# SB2232_v02.net
KiCad netlist of a schematic drawn in Altium Designer
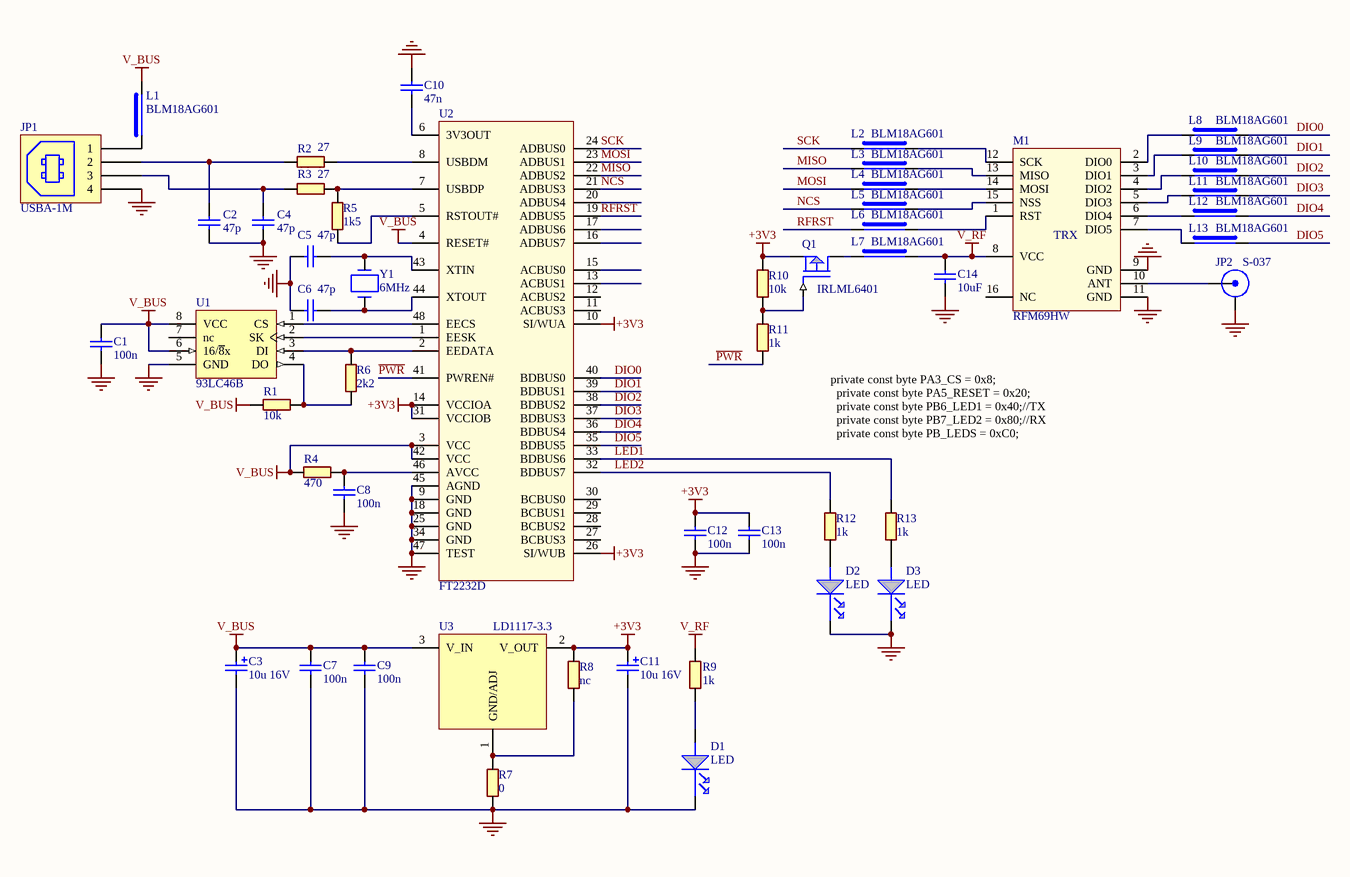
[diagram p0: SB2232_v02.SchDoc]

(export (version "E")
  (design (tool "Eeschema 10.0.6"))
  (components
    (comp (ref "C1") (value "100n") (footprint "CAPC1608X08N") (libsource (lib "Discrete") (part "CAPN")))
    (comp (ref "C2") (value "47p") (footprint "CAPC1608X08N") (libsource (lib "Discrete") (part "CAPN")))
    (comp (ref "C3") (value "10u 16V") (footprint "CAPMP3217X18N") (libsource (lib "Discrete") (part "CAPP")))
    (comp (ref "C4") (value "47p") (footprint "CAPC1608X08N") (libsource (lib "Discrete") (part "CAPN")))
    (comp (ref "C5") (value "47p") (footprint "CAPC1608X08N") (libsource (lib "Discrete") (part "CAPN")))
    (comp (ref "C6") (value "47p") (footprint "CAPC1608X08N") (libsource (lib "Discrete") (part "CAPN")))
    (comp (ref "C7") (value "100n") (footprint "CAPC1608X08N") (libsource (lib "Discrete") (part "CAPN")))
    (comp (ref "C8") (value "100n") (footprint "CAPC1608X08N") (libsource (lib "Discrete") (part "CAPN")))
    (comp (ref "C9") (value "100n") (footprint "CAPC1608X08N") (libsource (lib "Discrete") (part "CAPN")))
    (comp (ref "C10") (value "47n") (footprint "CAPC1608X08N") (libsource (lib "Discrete") (part "CAPN")))
    (comp (ref "C11")
      (value "10u 16V")
      (footprint "CAPMP3217X18N")
      (libsource (lib "Discrete") (part "CAPP"))
    )
    (comp (ref "C12") (value "100n") (footprint "CAPC1608X08N") (libsource (lib "Discrete") (part "CAPN")))
    (comp (ref "C13") (value "100n") (footprint "CAPC1608X08N") (libsource (lib "Discrete") (part "CAPN")))
    (comp (ref "C14") (value "10uF") (footprint "CAPC2012X11N") (libsource (lib "Discrete") (part "CAPN")))
    (comp (ref "D1") (value "LED") (footprint "LEDC200X125X80L40N") (libsource (lib "Discrete") (part "LED")))
    (comp (ref "D2") (value "LED") (footprint "LEDC200X125X80L40N") (libsource (lib "Discrete") (part "LED")))
    (comp (ref "D3") (value "LED") (footprint "LEDC200X125X80L40N") (libsource (lib "Discrete") (part "LED")))
    (comp (ref "JP1")
      (value "USBA-1M")
      (footprint "USB_A_M_SMD")
      (description "USB_connector")
      (libsource (lib "jlink072") (part "USB_conn"))
    )
    (comp (ref "JP2")
      (value "S-037")
      (footprint "S-037_3D")
      (description "RF Connector")
      (libsource (lib "RFM_PS_V01") (part "BNC"))
    )
    (comp (ref "L1")
      (value "BLM18AG601")
      (footprint "INDC1608X10N")
      (libsource (lib "RFM_PS_V01") (part "SUPRESOR"))
    )
    (comp (ref "L2")
      (value "BLM18AG601")
      (footprint "INDC1608X10N")
      (libsource (lib "RFM_PS_V01") (part "SUPRESOR"))
    )
    (comp (ref "L3")
      (value "BLM18AG601")
      (footprint "INDC1608X10N")
      (libsource (lib "RFM_PS_V01") (part "SUPRESOR"))
    )
    (comp (ref "L4")
      (value "BLM18AG601")
      (footprint "INDC1608X10N")
      (libsource (lib "RFM_PS_V01") (part "SUPRESOR"))
    )
    (comp (ref "L5")
      (value "BLM18AG601")
      (footprint "INDC1608X10N")
      (libsource (lib "RFM_PS_V01") (part "SUPRESOR"))
    )
    (comp (ref "L6")
      (value "BLM18AG601")
      (footprint "INDC1608X10N")
      (libsource (lib "RFM_PS_V01") (part "SUPRESOR"))
    )
    (comp (ref "L7")
      (value "BLM18AG601")
      (footprint "INDC1608X10N")
      (libsource (lib "RFM_PS_V01") (part "SUPRESOR"))
    )
    (comp (ref "L8")
      (value "BLM18AG601")
      (footprint "INDC1608X10N")
      (libsource (lib "RFM_PS_V01") (part "SUPRESOR"))
    )
    (comp (ref "L9")
      (value "BLM18AG601")
      (footprint "INDC1608X10N")
      (libsource (lib "RFM_PS_V01") (part "SUPRESOR"))
    )
    (comp (ref "L10")
      (value "BLM18AG601")
      (footprint "INDC1608X10N")
      (libsource (lib "RFM_PS_V01") (part "SUPRESOR"))
    )
    (comp (ref "L11")
      (value "BLM18AG601")
      (footprint "INDC1608X10N")
      (libsource (lib "RFM_PS_V01") (part "SUPRESOR"))
    )
    (comp (ref "L12")
      (value "BLM18AG601")
      (footprint "INDC1608X10N")
      (libsource (lib "RFM_PS_V01") (part "SUPRESOR"))
    )
    (comp (ref "L13")
      (value "BLM18AG601")
      (footprint "INDC1608X10N")
      (libsource (lib "RFM_PS_V01") (part "SUPRESOR"))
    )
    (comp (ref "M1")
      (value "RFM69HW")
      (footprint "LGA16_RFM69")
      (libsource (lib "CLAP_M505_WL_BP_V22") (part "RFM69HW_V13_2"))
    )
    (comp (ref "Q1")
      (value "IRLML6401")
      (footprint "SOT-23")
      (libsource (lib "CLAP_M505_WL_BP_V22") (part "MOSF-P"))
    )
    (comp (ref "R1") (value "10k") (footprint "RESC1608X06N") (libsource (lib "") (part "RES_2")))
    (comp (ref "R2") (value "27") (footprint "RESC1608X06N") (libsource (lib "") (part "RES_1")))
    (comp (ref "R3") (value "27") (footprint "RESC1608X06N") (libsource (lib "") (part "RES_1")))
    (comp (ref "R4") (value "470") (footprint "RESC1608X06N") (libsource (lib "") (part "RES_1")))
    (comp (ref "R5") (value "1k5") (footprint "RESC1608X06N") (libsource (lib "Discrete") (part "RES")))
    (comp (ref "R6") (value "2k2") (footprint "RESC1608X06N") (libsource (lib "Discrete") (part "RES")))
    (comp (ref "R7") (value "0") (footprint "RESC1608X06N") (libsource (lib "Discrete") (part "RES")))
    (comp (ref "R8") (value "nc") (footprint "RESC1608X06N") (libsource (lib "Discrete") (part "RES")))
    (comp (ref "R9") (value "1k") (footprint "RESC1608X06N") (libsource (lib "") (part "RES_3")))
    (comp (ref "R10") (value "10k") (footprint "RESC1608X06N") (libsource (lib "Discrete") (part "RES")))
    (comp (ref "R11") (value "1k") (footprint "RESC1608X06N") (libsource (lib "Discrete") (part "RES")))
    (comp (ref "R12") (value "1k") (footprint "RESC1608X06N") (libsource (lib "") (part "RES_3")))
    (comp (ref "R13") (value "1k") (footprint "RESC1608X06N") (libsource (lib "Discrete") (part "RES")))
    (comp (ref "U1")
      (value "93LC46B")
      (footprint "SOIC127P600X175-8N")
      (description "3-wire EEPROM")
      (libsource (lib "ICs") (part "93C56"))
    )
    (comp (ref "U2")
      (value "FT2232D")
      (footprint "TSQFP50P900X900X160-48N")
      (libsource (lib "SB") (part "FT2232D"))
    )
    (comp (ref "U3")
      (value "LD1117-3.3")
      (footprint "SOT230P700X180-4N")
      (libsource (lib "RFM_PS_V01") (part "LM1117_3.3"))
    )
    (comp (ref "Y1")
      (value "6MHz")
      (footprint "XTAL_HC49P488W45L1117T490H350")
      (libsource (lib "Discrete") (part "Y"))
    )
  )
  (nets
    (net (code "1") (name "+3V3") (class "Default")
      (node (ref "C11") (pin "2") (pinfunction "2_2") (pintype "passive"))
      (node (ref "C12") (pin "1") (pinfunction "1_1") (pintype "passive"))
      (node (ref "C13") (pin "1") (pinfunction "1_1") (pintype "passive"))
      (node (ref "Q1") (pin "3") (pinfunction "SOURCE_3") (pintype "passive"))
      (node (ref "R10") (pin "2") (pinfunction "2_2") (pintype "passive"))
      (node (ref "R8") (pin "2") (pinfunction "2_2") (pintype "passive"))
      (node (ref "U2") (pin "10") (pinfunction "SI/WUA_10") (pintype "passive"))
      (node (ref "U2") (pin "14") (pinfunction "VCCIOA_14") (pintype "passive"))
      (node (ref "U2") (pin "26") (pinfunction "SI/WUB_26") (pintype "passive"))
      (node (ref "U2") (pin "31") (pinfunction "VCCIOB_31") (pintype "passive"))
      (node (ref "U3") (pin "2") (pinfunction "V_OUT_2") (pintype "passive"))
    )
    (net (code "2") (name "/DIO0") (class "Default")
      (node (ref "L8") (pin "2") (pinfunction "2_2") (pintype "passive"))
      (node (ref "U2") (pin "40") (pinfunction "BDBUS0_40") (pintype "passive"))
    )
    (net (code "3") (name "/DIO1") (class "Default")
      (node (ref "L9") (pin "2") (pinfunction "2_2") (pintype "passive"))
      (node (ref "U2") (pin "39") (pinfunction "BDBUS1_39") (pintype "passive"))
    )
    (net (code "4") (name "/DIO2") (class "Default")
      (node (ref "L10") (pin "2") (pinfunction "2_2") (pintype "passive"))
      (node (ref "U2") (pin "38") (pinfunction "BDBUS2_38") (pintype "passive"))
    )
    (net (code "5") (name "/DIO3") (class "Default")
      (node (ref "L11") (pin "2") (pinfunction "2_2") (pintype "passive"))
      (node (ref "U2") (pin "37") (pinfunction "BDBUS3_37") (pintype "passive"))
    )
    (net (code "6") (name "/DIO4") (class "Default")
      (node (ref "L12") (pin "2") (pinfunction "2_2") (pintype "passive"))
      (node (ref "U2") (pin "36") (pinfunction "BDBUS4_36") (pintype "passive"))
    )
    (net (code "7") (name "/DIO5") (class "Default")
      (node (ref "L13") (pin "2") (pinfunction "2_2") (pintype "passive"))
      (node (ref "U2") (pin "35") (pinfunction "BDBUS5_35") (pintype "passive"))
    )
    (net (code "8") (name "/LED1") (class "Default")
      (node (ref "R13") (pin "2") (pinfunction "2_2") (pintype "passive"))
      (node (ref "U2") (pin "33") (pinfunction "BDBUS6_33") (pintype "passive"))
    )
    (net (code "9") (name "/LED2") (class "Default")
      (node (ref "R12") (pin "1") (pinfunction "1_1") (pintype "passive"))
      (node (ref "U2") (pin "32") (pinfunction "BDBUS7_32") (pintype "passive"))
    )
    (net (code "10") (name "/MISO") (class "Default")
      (node (ref "L3") (pin "1") (pinfunction "1_1") (pintype "passive"))
      (node (ref "U2") (pin "22") (pinfunction "ADBUS2_22") (pintype "passive"))
    )
    (net (code "11") (name "/MOSI") (class "Default")
      (node (ref "L4") (pin "1") (pinfunction "1_1") (pintype "passive"))
      (node (ref "U2") (pin "23") (pinfunction "ADBUS1_23") (pintype "passive"))
    )
    (net (code "12") (name "/NCS") (class "Default")
      (node (ref "L5") (pin "1") (pinfunction "1_1") (pintype "passive"))
      (node (ref "U2") (pin "21") (pinfunction "ADBUS3_21") (pintype "passive"))
    )
    (net (code "13") (name "/RFRST") (class "Default")
      (node (ref "L6") (pin "1") (pinfunction "1_1") (pintype "passive"))
      (node (ref "U2") (pin "19") (pinfunction "ADBUS5_19") (pintype "passive"))
    )
    (net (code "14") (name "/SCK") (class "Default")
      (node (ref "L2") (pin "1") (pinfunction "1_1") (pintype "passive"))
      (node (ref "U2") (pin "24") (pinfunction "ADBUS0_24") (pintype "passive"))
    )
    (net (code "15") (name "/~{PWR}") (class "Default")
      (node (ref "R11") (pin "1") (pinfunction "1_1") (pintype "passive"))
      (node (ref "U2") (pin "41") (pinfunction "PWREN#_41") (pintype "passive"))
    )
    (net (code "16") (name "GND") (class "Default")
      (node (ref "C1") (pin "2") (pinfunction "2_2") (pintype "passive"))
      (node (ref "C10") (pin "1") (pinfunction "1_1") (pintype "passive"))
      (node (ref "C11") (pin "1") (pinfunction "1_1") (pintype "passive"))
      (node (ref "C12") (pin "2") (pinfunction "2_2") (pintype "passive"))
      (node (ref "C13") (pin "2") (pinfunction "2_2") (pintype "passive"))
      (node (ref "C14") (pin "2") (pinfunction "2_2") (pintype "passive"))
      (node (ref "C2") (pin "2") (pinfunction "2_2") (pintype "passive"))
      (node (ref "C3") (pin "1") (pinfunction "1_1") (pintype "passive"))
      (node (ref "C4") (pin "2") (pinfunction "2_2") (pintype "passive"))
      (node (ref "C5") (pin "1") (pinfunction "1_1") (pintype "passive"))
      (node (ref "C6") (pin "1") (pinfunction "1_1") (pintype "passive"))
      (node (ref "C7") (pin "2") (pinfunction "2_2") (pintype "passive"))
      (node (ref "C8") (pin "2") (pinfunction "2_2") (pintype "passive"))
      (node (ref "C9") (pin "2") (pinfunction "2_2") (pintype "passive"))
      (node (ref "D1") (pin "K") (pinfunction "CATHODE_K") (pintype "passive"))
      (node (ref "D2") (pin "K") (pinfunction "CATHODE_K") (pintype "passive"))
      (node (ref "D3") (pin "K") (pinfunction "CATHODE_K") (pintype "passive"))
      (node (ref "JP1") (pin "4") (pinfunction "4_4") (pintype "passive"))
      (node (ref "JP2") (pin "2") (pinfunction "Y_2") (pintype "passive"))
      (node (ref "M1") (pin "11") (pinfunction "GND_11") (pintype "passive"))
      (node (ref "M1") (pin "9") (pinfunction "GND_9") (pintype "passive"))
      (node (ref "R7") (pin "1") (pinfunction "1_1") (pintype "passive"))
      (node (ref "U1") (pin "5") (pinfunction "GND_5") (pintype "power_in"))
      (node (ref "U2") (pin "18") (pinfunction "GND_18") (pintype "passive"))
      (node (ref "U2") (pin "25") (pinfunction "GND_25") (pintype "passive"))
      (node (ref "U2") (pin "34") (pinfunction "GND_34") (pintype "passive"))
      (node (ref "U2") (pin "45") (pinfunction "AGND_45") (pintype "passive"))
      (node (ref "U2") (pin "47") (pinfunction "TEST_47") (pintype "passive"))
      (node (ref "U2") (pin "9") (pinfunction "GND_9") (pintype "passive"))
    )
    (net (code "17") (name "Net-(C2-Pad1)") (class "Default")
      (node (ref "C2") (pin "1") (pinfunction "1_1") (pintype "passive"))
      (node (ref "JP1") (pin "2") (pinfunction "2_2") (pintype "passive"))
      (node (ref "R2") (pin "1") (pinfunction "1_1") (pintype "passive"))
    )
    (net (code "18") (name "Net-(C4-Pad1)") (class "Default")
      (node (ref "C4") (pin "1") (pinfunction "1_1") (pintype "passive"))
      (node (ref "JP1") (pin "3") (pinfunction "3_3") (pintype "passive"))
      (node (ref "R3") (pin "1") (pinfunction "1_1") (pintype "passive"))
    )
    (net (code "19") (name "Net-(D1-ANODE)") (class "Default")
      (node (ref "D1") (pin "A") (pinfunction "ANODE_A") (pintype "passive"))
      (node (ref "R9") (pin "2") (pinfunction "2_2") (pintype "passive"))
    )
    (net (code "20") (name "Net-(D2-ANODE)") (class "Default")
      (node (ref "D2") (pin "A") (pinfunction "ANODE_A") (pintype "passive"))
      (node (ref "R12") (pin "2") (pinfunction "2_2") (pintype "passive"))
    )
    (net (code "21") (name "Net-(D3-ANODE)") (class "Default")
      (node (ref "D3") (pin "A") (pinfunction "ANODE_A") (pintype "passive"))
      (node (ref "R13") (pin "1") (pinfunction "1_1") (pintype "passive"))
    )
    (net (code "22") (name "Net-(JP1-Pad1)") (class "Default")
      (node (ref "JP1") (pin "1") (pinfunction "1_1") (pintype "passive"))
      (node (ref "L1") (pin "1") (pinfunction "1_1") (pintype "passive"))
    )
    (net (code "23") (name "Net-(JP2-X)") (class "Default")
      (node (ref "JP2") (pin "1") (pinfunction "X_1") (pintype "passive"))
      (node (ref "M1") (pin "10") (pinfunction "ANT_10") (pintype "passive"))
    )
    (net (code "24") (name "Net-(M1-DIO0)") (class "Default")
      (node (ref "L8") (pin "1") (pinfunction "1_1") (pintype "passive"))
      (node (ref "M1") (pin "2") (pinfunction "DIO0_2") (pintype "passive"))
    )
    (net (code "25") (name "Net-(M1-DIO1)") (class "Default")
      (node (ref "L9") (pin "1") (pinfunction "1_1") (pintype "passive"))
      (node (ref "M1") (pin "3") (pinfunction "DIO1_3") (pintype "passive"))
    )
    (net (code "26") (name "Net-(M1-DIO2)") (class "Default")
      (node (ref "L10") (pin "1") (pinfunction "1_1") (pintype "passive"))
      (node (ref "M1") (pin "4") (pinfunction "DIO2_4") (pintype "passive"))
    )
    (net (code "27") (name "Net-(M1-DIO3)") (class "Default")
      (node (ref "L11") (pin "1") (pinfunction "1_1") (pintype "passive"))
      (node (ref "M1") (pin "5") (pinfunction "DIO3_5") (pintype "passive"))
    )
    (net (code "28") (name "Net-(M1-DIO4)") (class "Default")
      (node (ref "L12") (pin "1") (pinfunction "1_1") (pintype "passive"))
      (node (ref "M1") (pin "6") (pinfunction "DIO4_6") (pintype "passive"))
    )
    (net (code "29") (name "Net-(M1-DIO5)") (class "Default")
      (node (ref "L13") (pin "1") (pinfunction "1_1") (pintype "passive"))
      (node (ref "M1") (pin "7") (pinfunction "DIO5_7") (pintype "passive"))
    )
    (net (code "30") (name "Net-(M1-MISO)") (class "Default")
      (node (ref "L3") (pin "2") (pinfunction "2_2") (pintype "passive"))
      (node (ref "M1") (pin "13") (pinfunction "MISO_13") (pintype "passive"))
    )
    (net (code "31") (name "Net-(M1-MOSI)") (class "Default")
      (node (ref "L4") (pin "2") (pinfunction "2_2") (pintype "passive"))
      (node (ref "M1") (pin "14") (pinfunction "MOSI_14") (pintype "passive"))
    )
    (net (code "32") (name "Net-(M1-NSS)") (class "Default")
      (node (ref "L5") (pin "2") (pinfunction "2_2") (pintype "passive"))
      (node (ref "M1") (pin "15") (pinfunction "NSS_15") (pintype "passive"))
    )
    (net (code "33") (name "Net-(M1-RST)") (class "Default")
      (node (ref "L6") (pin "2") (pinfunction "2_2") (pintype "passive"))
      (node (ref "M1") (pin "1") (pinfunction "RST_1") (pintype "passive"))
    )
    (net (code "34") (name "Net-(M1-SCK)") (class "Default")
      (node (ref "L2") (pin "2") (pinfunction "2_2") (pintype "passive"))
      (node (ref "M1") (pin "12") (pinfunction "SCK_12") (pintype "passive"))
    )
    (net (code "35") (name "Net-(Q1-DRAIN)") (class "Default")
      (node (ref "L7") (pin "1") (pinfunction "1_1") (pintype "passive"))
      (node (ref "Q1") (pin "2") (pinfunction "DRAIN_2") (pintype "passive"))
    )
    (net (code "36") (name "Net-(Q1-GATE)") (class "Default")
      (node (ref "Q1") (pin "1") (pinfunction "GATE_1") (pintype "input"))
      (node (ref "R10") (pin "1") (pinfunction "1_1") (pintype "passive"))
      (node (ref "R11") (pin "2") (pinfunction "2_2") (pintype "passive"))
    )
    (net (code "37") (name "Net-(U1-CS)") (class "Default")
      (node (ref "U1") (pin "1") (pinfunction "CS_1") (pintype "input"))
      (node (ref "U2") (pin "48") (pinfunction "EECS_48") (pintype "passive"))
    )
    (net (code "38") (name "Net-(U1-DI)") (class "Default")
      (node (ref "R6") (pin "2") (pinfunction "2_2") (pintype "passive"))
      (node (ref "U1") (pin "3") (pinfunction "DI_3") (pintype "input"))
      (node (ref "U2") (pin "2") (pinfunction "EEDATA_2") (pintype "passive"))
    )
    (net (code "39") (name "Net-(U1-DO)") (class "Default")
      (node (ref "R1") (pin "1") (pinfunction "1_1") (pintype "passive"))
      (node (ref "R6") (pin "1") (pinfunction "1_1") (pintype "passive"))
      (node (ref "U1") (pin "4") (pinfunction "DO_4") (pintype "output"))
    )
    (net (code "40") (name "Net-(U1-SK)") (class "Default")
      (node (ref "U1") (pin "2") (pinfunction "SK_2") (pintype "input"))
      (node (ref "U2") (pin "1") (pinfunction "EESK_1") (pintype "passive"))
    )
    (net (code "41") (name "Net-(U2-3V3OUT)") (class "Default")
      (node (ref "C10") (pin "2") (pinfunction "2_2") (pintype "passive"))
      (node (ref "U2") (pin "6") (pinfunction "3V3OUT_6") (pintype "passive"))
    )
    (net (code "42") (name "Net-(U2-AVCC)") (class "Default")
      (node (ref "C8") (pin "1") (pinfunction "1_1") (pintype "passive"))
      (node (ref "R4") (pin "2") (pinfunction "2_2") (pintype "passive"))
      (node (ref "U2") (pin "46") (pinfunction "AVCC_46") (pintype "passive"))
    )
    (net (code "43") (name "Net-(U2-RSTOUT#)") (class "Default")
      (node (ref "R5") (pin "1") (pinfunction "1_1") (pintype "passive"))
      (node (ref "U2") (pin "5") (pinfunction "RSTOUT#_5") (pintype "passive"))
    )
    (net (code "44") (name "Net-(U2-USBDM)") (class "Default")
      (node (ref "R2") (pin "2") (pinfunction "2_2") (pintype "passive"))
      (node (ref "U2") (pin "8") (pinfunction "USBDM_8") (pintype "passive"))
    )
    (net (code "45") (name "Net-(U2-USBDP)") (class "Default")
      (node (ref "R3") (pin "2") (pinfunction "2_2") (pintype "passive"))
      (node (ref "R5") (pin "2") (pinfunction "2_2") (pintype "passive"))
      (node (ref "U2") (pin "7") (pinfunction "USBDP_7") (pintype "passive"))
    )
    (net (code "46") (name "Net-(U2-XTIN)") (class "Default")
      (node (ref "C5") (pin "2") (pinfunction "2_2") (pintype "passive"))
      (node (ref "U2") (pin "43") (pinfunction "XTIN_43") (pintype "passive"))
      (node (ref "Y1") (pin "2") (pinfunction "2_2") (pintype "passive"))
    )
    (net (code "47") (name "Net-(U2-XTOUT)") (class "Default")
      (node (ref "C6") (pin "2") (pinfunction "2_2") (pintype "passive"))
      (node (ref "U2") (pin "44") (pinfunction "XTOUT_44") (pintype "passive"))
      (node (ref "Y1") (pin "1") (pinfunction "1_1") (pintype "passive"))
    )
    (net (code "48") (name "Net-(U3-GND{slash}ADJ)") (class "Default")
      (node (ref "R7") (pin "2") (pinfunction "2_2") (pintype "passive"))
      (node (ref "R8") (pin "1") (pinfunction "1_1") (pintype "passive"))
      (node (ref "U3") (pin "1") (pinfunction "GND/ADJ_1") (pintype "passive"))
    )
    (net (code "49") (name "V_BUS") (class "Default")
      (node (ref "C1") (pin "1") (pinfunction "1_1") (pintype "passive"))
      (node (ref "C3") (pin "2") (pinfunction "2_2") (pintype "passive"))
      (node (ref "C7") (pin "1") (pinfunction "1_1") (pintype "passive"))
      (node (ref "C9") (pin "1") (pinfunction "1_1") (pintype "passive"))
      (node (ref "L1") (pin "2") (pinfunction "2_2") (pintype "passive"))
      (node (ref "R1") (pin "2") (pinfunction "2_2") (pintype "passive"))
      (node (ref "R4") (pin "1") (pinfunction "1_1") (pintype "passive"))
      (node (ref "U1") (pin "6") (pinfunction "16/~{8}x_6") (pintype "input"))
      (node (ref "U1") (pin "8") (pinfunction "VCC_8") (pintype "power_in"))
      (node (ref "U2") (pin "3") (pinfunction "VCC_3") (pintype "passive"))
      (node (ref "U2") (pin "4") (pinfunction "RESET#_4") (pintype "passive"))
      (node (ref "U2") (pin "42") (pinfunction "VCC_42") (pintype "passive"))
      (node (ref "U3") (pin "3") (pinfunction "V_IN_3") (pintype "passive"))
    )
    (net (code "50") (name "V_RF") (class "Default")
      (node (ref "C14") (pin "1") (pinfunction "1_1") (pintype "passive"))
      (node (ref "L7") (pin "2") (pinfunction "2_2") (pintype "passive"))
      (node (ref "M1") (pin "8") (pinfunction "VCC_8") (pintype "passive"))
      (node (ref "R9") (pin "1") (pinfunction "1_1") (pintype "passive"))
    )
    (net (code "51") (name "unconnected-(M1-NC-Pad16)") (class "Default")
      (node (ref "M1") (pin "16") (pinfunction "NC_16") (pintype "passive"))
    )
    (net (code "52") (name "unconnected-(U1-nc-Pad7)") (class "Default")
      (node (ref "U1") (pin "7") (pinfunction "nc_7") (pintype "passive"))
    )
    (net (code "53") (name "unconnected-(U2-ACBUS0-Pad15)") (class "Default")
      (node (ref "U2") (pin "15") (pinfunction "ACBUS0_15") (pintype "passive"))
    )
    (net (code "54") (name "unconnected-(U2-ACBUS1-Pad13)") (class "Default")
      (node (ref "U2") (pin "13") (pinfunction "ACBUS1_13") (pintype "passive"))
    )
    (net (code "55") (name "unconnected-(U2-ACBUS2-Pad12)") (class "Default")
      (node (ref "U2") (pin "12") (pinfunction "ACBUS2_12") (pintype "passive"))
    )
    (net (code "56") (name "unconnected-(U2-ACBUS3-Pad11)") (class "Default")
      (node (ref "U2") (pin "11") (pinfunction "ACBUS3_11") (pintype "passive"))
    )
    (net (code "57") (name "unconnected-(U2-ADBUS4-Pad20)") (class "Default")
      (node (ref "U2") (pin "20") (pinfunction "ADBUS4_20") (pintype "passive"))
    )
    (net (code "58") (name "unconnected-(U2-ADBUS6-Pad17)") (class "Default")
      (node (ref "U2") (pin "17") (pinfunction "ADBUS6_17") (pintype "passive"))
    )
    (net (code "59") (name "unconnected-(U2-ADBUS7-Pad16)") (class "Default")
      (node (ref "U2") (pin "16") (pinfunction "ADBUS7_16") (pintype "passive"))
    )
    (net (code "60") (name "unconnected-(U2-BCBUS0-Pad30)") (class "Default")
      (node (ref "U2") (pin "30") (pinfunction "BCBUS0_30") (pintype "passive"))
    )
    (net (code "61") (name "unconnected-(U2-BCBUS1-Pad29)") (class "Default")
      (node (ref "U2") (pin "29") (pinfunction "BCBUS1_29") (pintype "passive"))
    )
    (net (code "62") (name "unconnected-(U2-BCBUS2-Pad28)") (class "Default")
      (node (ref "U2") (pin "28") (pinfunction "BCBUS2_28") (pintype "passive"))
    )
    (net (code "63") (name "unconnected-(U2-BCBUS3-Pad27)") (class "Default")
      (node (ref "U2") (pin "27") (pinfunction "BCBUS3_27") (pintype "passive"))
    )
  )
)
